# balloon-v02-matt.net
KiCad netlist of a schematic drawn in EAGLE
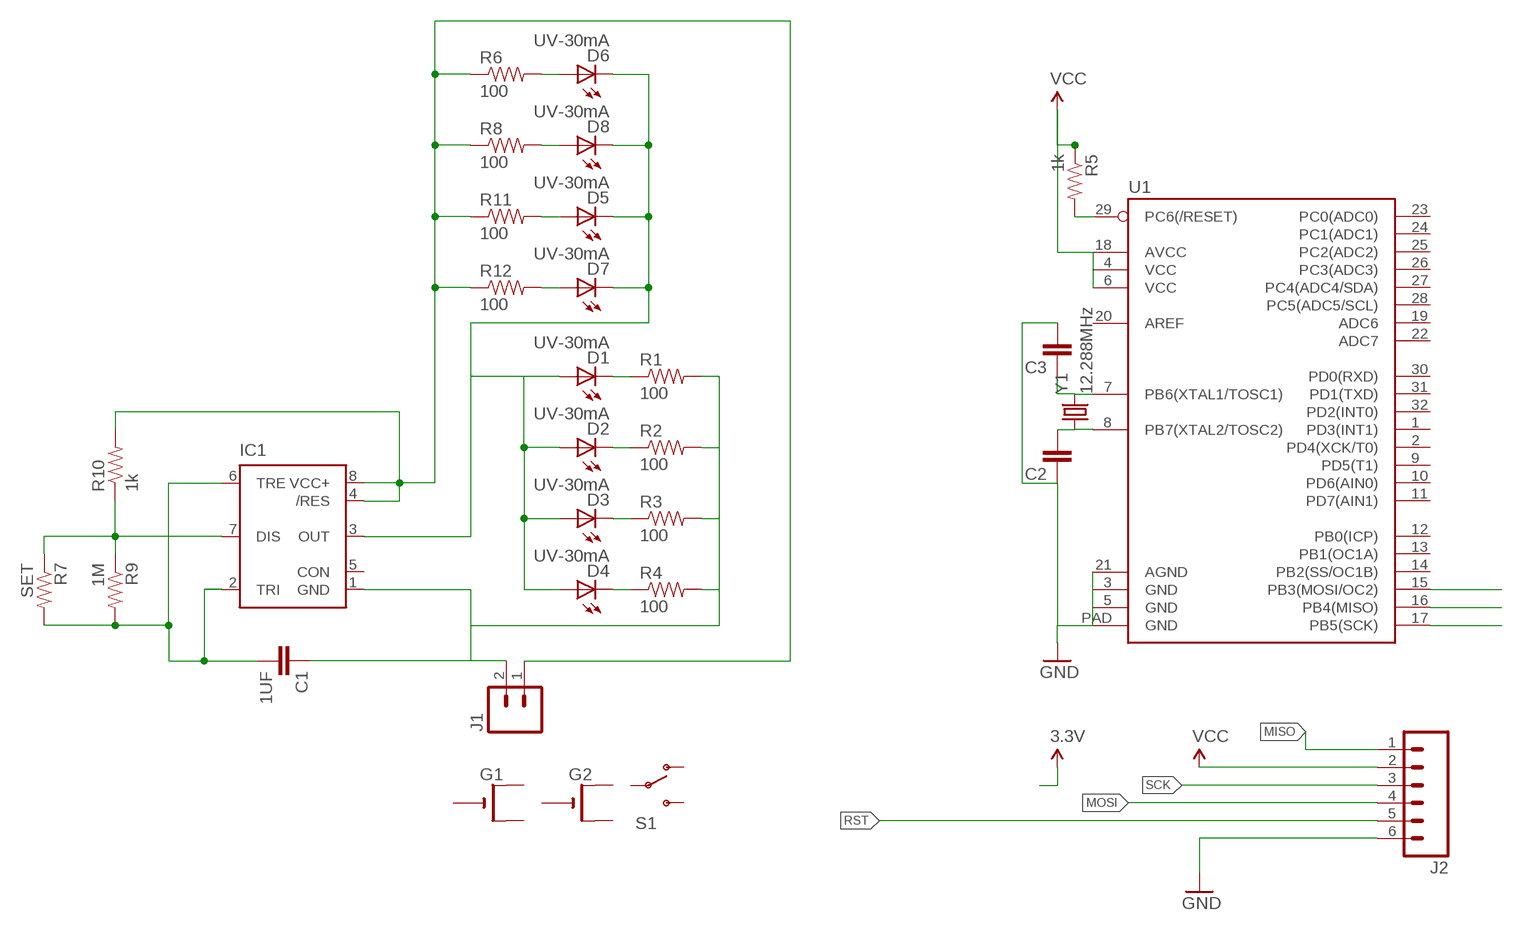
[diagram p0: schematic, sheet 1]

(export (version "E")
  (design (tool "Eeschema 10.0.6"))
  (components
    (comp (ref "C1")
      (value "1UF")
      (footprint "eagle-import:0603-CAP")
      (libsource (lib "eagle-import") (part "CAP0603-CAP"))
    )
    (comp (ref "C2")
      (value "CAP0603-CAP")
      (footprint "eagle-import:0603-CAP")
      (libsource (lib "eagle-import") (part "SparkFun-Passives_CAP0603-CAP"))
    )
    (comp (ref "C3")
      (value "CAP0603-CAP")
      (footprint "eagle-import:0603-CAP")
      (libsource (lib "eagle-import") (part "SparkFun-Passives_CAP0603-CAP"))
    )
    (comp (ref "D1")
      (value "UV-30mA")
      (footprint "eagle-import:CHIPLED_0603")
      (libsource (lib "eagle-import") (part "LEDCHIPLED_0603"))
    )
    (comp (ref "D2")
      (value "UV-30mA")
      (footprint "eagle-import:CHIPLED_0603")
      (libsource (lib "eagle-import") (part "LEDCHIPLED_0603"))
    )
    (comp (ref "D3")
      (value "UV-30mA")
      (footprint "eagle-import:CHIPLED_0603")
      (libsource (lib "eagle-import") (part "LEDCHIPLED_0603"))
    )
    (comp (ref "D4")
      (value "UV-30mA")
      (footprint "eagle-import:CHIPLED_0603")
      (libsource (lib "eagle-import") (part "LEDCHIPLED_0603"))
    )
    (comp (ref "D5")
      (value "UV-30mA")
      (footprint "eagle-import:CHIPLED_0603")
      (libsource (lib "eagle-import") (part "LEDCHIPLED_0603"))
    )
    (comp (ref "D6")
      (value "UV-30mA")
      (footprint "eagle-import:CHIPLED_0603")
      (libsource (lib "eagle-import") (part "LEDCHIPLED_0603"))
    )
    (comp (ref "D7")
      (value "UV-30mA")
      (footprint "eagle-import:CHIPLED_0603")
      (libsource (lib "eagle-import") (part "LEDCHIPLED_0603"))
    )
    (comp (ref "D8")
      (value "UV-30mA")
      (footprint "eagle-import:CHIPLED_0603")
      (libsource (lib "eagle-import") (part "LEDCHIPLED_0603"))
    )
    (comp (ref "G1")
      (value "CR2032SMT")
      (footprint "eagle-import:CR2032-SMD")
      (libsource (lib "eagle-import") (part "CR2032SMT"))
    )
    (comp (ref "G2")
      (value "CR2032SMT")
      (footprint "eagle-import:CR2032-SMD")
      (libsource (lib "eagle-import") (part "CR2032SMT"))
    )
    (comp (ref "IC1")
      (value "NE555D")
      (footprint "eagle-import:SO08")
      (libsource (lib "eagle-import") (part "NE555D"))
    )
    (comp (ref "J1")
      (value "M02PTH3")
      (footprint "eagle-import:1X02_LONGPADS")
      (libsource (lib "eagle-import") (part "M02PTH3"))
    )
    (comp (ref "J2")
      (value "M06SIP_LOCK")
      (footprint "eagle-import:1X06-SIP_LOCK")
      (libsource (lib "eagle-import") (part "M06SIP_LOCK"))
    )
    (comp (ref "R1")
      (value "100")
      (footprint "eagle-import:0603-RES")
      (libsource (lib "eagle-import") (part "RESISTOR0603-RES"))
    )
    (comp (ref "R2")
      (value "100")
      (footprint "eagle-import:0603-RES")
      (libsource (lib "eagle-import") (part "RESISTOR0603-RES"))
    )
    (comp (ref "R3")
      (value "100")
      (footprint "eagle-import:0603-RES")
      (libsource (lib "eagle-import") (part "RESISTOR0603-RES"))
    )
    (comp (ref "R4")
      (value "100")
      (footprint "eagle-import:0603-RES")
      (libsource (lib "eagle-import") (part "RESISTOR0603-RES"))
    )
    (comp (ref "R5")
      (value "1k")
      (footprint "eagle-import:0603-RES")
      (libsource (lib "eagle-import") (part "RESISTOR0603-RES"))
    )
    (comp (ref "R6")
      (value "100")
      (footprint "eagle-import:0603-RES")
      (libsource (lib "eagle-import") (part "RESISTOR0603-RES"))
    )
    (comp (ref "R7")
      (value "SET")
      (footprint "eagle-import:AXIAL-0.3-KIT")
      (libsource (lib "eagle-import") (part "RESISTORKIT"))
    )
    (comp (ref "R8")
      (value "100")
      (footprint "eagle-import:0603-RES")
      (libsource (lib "eagle-import") (part "RESISTOR0603-RES"))
    )
    (comp (ref "R9")
      (value "1M")
      (footprint "eagle-import:0603-RES")
      (libsource (lib "eagle-import") (part "RESISTOR0603-RES"))
    )
    (comp (ref "R10")
      (value "1k")
      (footprint "eagle-import:0603-RES")
      (libsource (lib "eagle-import") (part "RESISTOR0603-RES"))
    )
    (comp (ref "R11")
      (value "100")
      (footprint "eagle-import:0603-RES")
      (libsource (lib "eagle-import") (part "RESISTOR0603-RES"))
    )
    (comp (ref "R12")
      (value "100")
      (footprint "eagle-import:0603-RES")
      (libsource (lib "eagle-import") (part "RESISTOR0603-RES"))
    )
    (comp (ref "S1")
      (value "SWITCH-SPDT-SMD-A")
      (footprint "eagle-import:SWITCH-SPST-SMD-A")
      (libsource (lib "eagle-import") (part "SWITCH-SPDT-SMD-A"))
    )
    (comp (ref "U1")
      (value "ATMEGA328P_MLFMLF32")
      (footprint "eagle-import:MLF32-PAD")
      (libsource (lib "eagle-import") (part "ATMEGA328P_MLFMLF32"))
    )
    (comp (ref "Y1")
      (value "12.288MHz")
      (footprint "eagle-import:CRYSTAL-SMD-5X3")
      (libsource (lib "eagle-import") (part "CRYSTALCRYSTAL-SMD-5X3-12.288MHZ"))
    )
  )
  (nets
    (net (code "2") (name "GND") (class "Default")
      (node (ref "C1") (pin "1") (pinfunction "1_1") (pintype "passive"))
      (node (ref "C2") (pin "1") (pinfunction "1_1") (pintype "passive"))
      (node (ref "C3") (pin "2") (pinfunction "2_2") (pintype "passive"))
      (node (ref "IC1") (pin "1") (pinfunction "GND_1") (pintype "power_in"))
      (node (ref "J1") (pin "2") (pinfunction "2_2") (pintype "passive"))
      (node (ref "J2") (pin "6") (pinfunction "6_6") (pintype "passive"))
      (node (ref "R1") (pin "2") (pinfunction "2_2") (pintype "passive"))
      (node (ref "R2") (pin "2") (pinfunction "2_2") (pintype "passive"))
      (node (ref "R3") (pin "2") (pinfunction "2_2") (pintype "passive"))
      (node (ref "R4") (pin "2") (pinfunction "2_2") (pintype "passive"))
      (node (ref "U1") (pin "21") (pinfunction "AGND_21") (pintype "bidirectional"))
      (node (ref "U1") (pin "3") (pinfunction "GND_3") (pintype "bidirectional"))
      (node (ref "U1") (pin "5") (pinfunction "GND_5") (pintype "bidirectional"))
      (node (ref "U1") (pin "PAD") (pinfunction "GND_PAD") (pintype "bidirectional"))
    )
    (net (code "3") (name "MISO") (class "Default")
      (node (ref "J2") (pin "1") (pinfunction "1_1") (pintype "passive"))
      (node (ref "U1") (pin "16") (pinfunction "PB4(MISO)_16") (pintype "bidirectional"))
    )
    (net (code "4") (name "MOSI") (class "Default")
      (node (ref "J2") (pin "4") (pinfunction "4_4") (pintype "passive"))
      (node (ref "U1") (pin "15") (pinfunction "PB3(MOSI/OC2)_15") (pintype "bidirectional"))
    )
    (net (code "5") (name "Net-(D1-PadC)") (class "Default")
      (node (ref "D1") (pin "C") (pinfunction "C_C") (pintype "passive"))
      (node (ref "R1") (pin "1") (pinfunction "1_1") (pintype "passive"))
    )
    (net (code "6") (name "Net-(D2-PadC)") (class "Default")
      (node (ref "D2") (pin "C") (pinfunction "C_C") (pintype "passive"))
      (node (ref "R2") (pin "1") (pinfunction "1_1") (pintype "passive"))
    )
    (net (code "7") (name "Net-(D3-PadC)") (class "Default")
      (node (ref "D3") (pin "C") (pinfunction "C_C") (pintype "passive"))
      (node (ref "R3") (pin "1") (pinfunction "1_1") (pintype "passive"))
    )
    (net (code "8") (name "Net-(D4-PadC)") (class "Default")
      (node (ref "D4") (pin "C") (pinfunction "C_C") (pintype "passive"))
      (node (ref "R4") (pin "1") (pinfunction "1_1") (pintype "passive"))
    )
    (net (code "9") (name "Net-(D5-PadA)") (class "Default")
      (node (ref "D5") (pin "A") (pinfunction "A_A") (pintype "passive"))
      (node (ref "R11") (pin "2") (pinfunction "2_2") (pintype "passive"))
    )
    (net (code "10") (name "Net-(D6-PadA)") (class "Default")
      (node (ref "D6") (pin "A") (pinfunction "A_A") (pintype "passive"))
      (node (ref "R6") (pin "2") (pinfunction "2_2") (pintype "passive"))
    )
    (net (code "11") (name "Net-(D7-PadA)") (class "Default")
      (node (ref "D7") (pin "A") (pinfunction "A_A") (pintype "passive"))
      (node (ref "R12") (pin "2") (pinfunction "2_2") (pintype "passive"))
    )
    (net (code "12") (name "Net-(D8-PadA)") (class "Default")
      (node (ref "D8") (pin "A") (pinfunction "A_A") (pintype "passive"))
      (node (ref "R8") (pin "2") (pinfunction "2_2") (pintype "passive"))
    )
    (net (code "13") (name "Net-(IC1-DIS)") (class "Default")
      (node (ref "IC1") (pin "7") (pinfunction "DIS_7") (pintype "input"))
      (node (ref "R10") (pin "1") (pinfunction "1_1") (pintype "passive"))
      (node (ref "R7") (pin "P$1") (pinfunction "1_P$1") (pintype "passive"))
      (node (ref "R9") (pin "1") (pinfunction "1_1") (pintype "passive"))
    )
    (net (code "14") (name "Net-(IC1-OUT)") (class "Default")
      (node (ref "D1") (pin "A") (pinfunction "A_A") (pintype "passive"))
      (node (ref "D2") (pin "A") (pinfunction "A_A") (pintype "passive"))
      (node (ref "D3") (pin "A") (pinfunction "A_A") (pintype "passive"))
      (node (ref "D4") (pin "A") (pinfunction "A_A") (pintype "passive"))
      (node (ref "D5") (pin "C") (pinfunction "C_C") (pintype "passive"))
      (node (ref "D6") (pin "C") (pinfunction "C_C") (pintype "passive"))
      (node (ref "D7") (pin "C") (pinfunction "C_C") (pintype "passive"))
      (node (ref "D8") (pin "C") (pinfunction "C_C") (pintype "passive"))
      (node (ref "IC1") (pin "3") (pinfunction "OUT_3") (pintype "output"))
    )
    (net (code "15") (name "Net-(IC1-TRE)") (class "Default")
      (node (ref "C1") (pin "2") (pinfunction "2_2") (pintype "passive"))
      (node (ref "IC1") (pin "2") (pinfunction "TRI_2") (pintype "input"))
      (node (ref "IC1") (pin "6") (pinfunction "TRE_6") (pintype "input"))
      (node (ref "R7") (pin "P$2") (pinfunction "2_P$2") (pintype "passive"))
      (node (ref "R9") (pin "2") (pinfunction "2_2") (pintype "passive"))
    )
    (net (code "16") (name "Net-(U1-PB6(XTAL1{slash}TOSC1))") (class "Default")
      (node (ref "C3") (pin "1") (pinfunction "1_1") (pintype "passive"))
      (node (ref "U1") (pin "7") (pinfunction "PB6(XTAL1/TOSC1)_7") (pintype "bidirectional"))
      (node (ref "Y1") (pin "3") (pinfunction "2_3") (pintype "passive"))
    )
    (net (code "17") (name "Net-(U1-PB7(XTAL2{slash}TOSC2))") (class "Default")
      (node (ref "C2") (pin "2") (pinfunction "2_2") (pintype "passive"))
      (node (ref "U1") (pin "8") (pinfunction "PB7(XTAL2/TOSC2)_8") (pintype "bidirectional"))
      (node (ref "Y1") (pin "1") (pinfunction "1_1") (pintype "passive"))
    )
    (net (code "18") (name "RST") (class "Default")
      (node (ref "J2") (pin "5") (pinfunction "5_5") (pintype "passive"))
      (node (ref "R5") (pin "2") (pinfunction "2_2") (pintype "passive"))
      (node (ref "U1") (pin "29") (pinfunction "PC6(/RESET)_29") (pintype "bidirectional"))
    )
    (net (code "19") (name "SCK") (class "Default")
      (node (ref "J2") (pin "3") (pinfunction "3_3") (pintype "passive"))
      (node (ref "U1") (pin "17") (pinfunction "PB5(SCK)_17") (pintype "bidirectional"))
    )
    (net (code "20") (name "VCC") (class "Default")
      (node (ref "IC1") (pin "4") (pinfunction "/RES_4") (pintype "input"))
      (node (ref "IC1") (pin "8") (pinfunction "VCC+_8") (pintype "power_in"))
      (node (ref "J1") (pin "1") (pinfunction "1_1") (pintype "passive"))
      (node (ref "J2") (pin "2") (pinfunction "2_2") (pintype "passive"))
      (node (ref "R10") (pin "2") (pinfunction "2_2") (pintype "passive"))
      (node (ref "R11") (pin "1") (pinfunction "1_1") (pintype "passive"))
      (node (ref "R12") (pin "1") (pinfunction "1_1") (pintype "passive"))
      (node (ref "R5") (pin "1") (pinfunction "1_1") (pintype "passive"))
      (node (ref "R6") (pin "1") (pinfunction "1_1") (pintype "passive"))
      (node (ref "R8") (pin "1") (pinfunction "1_1") (pintype "passive"))
      (node (ref "U1") (pin "18") (pinfunction "AVCC_18") (pintype "bidirectional"))
      (node (ref "U1") (pin "4") (pinfunction "VCC_4") (pintype "bidirectional"))
      (node (ref "U1") (pin "6") (pinfunction "VCC_6") (pintype "bidirectional"))
    )
    (net (code "21") (name "unconnected-(G1-+-Pad+$1)") (class "Default")
      (node (ref "G1") (pin "+$1") (pinfunction "+_+$1") (pintype "passive"))
    )
    (net (code "22") (name "unconnected-(G1-+1-Pad+$2)") (class "Default")
      (node (ref "G1") (pin "+$2") (pinfunction "+1_+$2") (pintype "passive"))
    )
    (net (code "23") (name "unconnected-(G1-Pad-)") (class "Default")
      (node (ref "G1") (pin "-") (pinfunction "-_-") (pintype "passive"))
    )
    (net (code "24") (name "unconnected-(G2-+-Pad+$1)") (class "Default")
      (node (ref "G2") (pin "+$1") (pinfunction "+_+$1") (pintype "passive"))
    )
    (net (code "25") (name "unconnected-(G2-+1-Pad+$2)") (class "Default")
      (node (ref "G2") (pin "+$2") (pinfunction "+1_+$2") (pintype "passive"))
    )
    (net (code "26") (name "unconnected-(G2-Pad-)") (class "Default")
      (node (ref "G2") (pin "-") (pinfunction "-_-") (pintype "passive"))
    )
    (net (code "27") (name "unconnected-(IC1-CON-Pad5)") (class "Default")
      (node (ref "IC1") (pin "5") (pinfunction "CON_5") (pintype "input"))
    )
    (net (code "28") (name "unconnected-(S1-O-Pad1)") (class "Default")
      (node (ref "S1") (pin "1") (pinfunction "O_1") (pintype "passive"))
    )
    (net (code "29") (name "unconnected-(S1-P-Pad2)") (class "Default")
      (node (ref "S1") (pin "2") (pinfunction "P_2") (pintype "passive"))
    )
    (net (code "30") (name "unconnected-(S1-S-Pad3)") (class "Default")
      (node (ref "S1") (pin "3") (pinfunction "S_3") (pintype "passive"))
    )
    (net (code "31") (name "unconnected-(U1-ADC6-Pad19)") (class "Default")
      (node (ref "U1") (pin "19") (pinfunction "ADC6_19") (pintype "bidirectional"))
    )
    (net (code "32") (name "unconnected-(U1-ADC7-Pad22)") (class "Default")
      (node (ref "U1") (pin "22") (pinfunction "ADC7_22") (pintype "bidirectional"))
    )
    (net (code "33") (name "unconnected-(U1-AREF-Pad20)") (class "Default")
      (node (ref "U1") (pin "20") (pinfunction "AREF_20") (pintype "bidirectional"))
    )
    (net (code "34") (name "unconnected-(U1-PB0(ICP)-Pad12)") (class "Default")
      (node (ref "U1") (pin "12") (pinfunction "PB0(ICP)_12") (pintype "bidirectional"))
    )
    (net (code "35") (name "unconnected-(U1-PB1(OC1A)-Pad13)") (class "Default")
      (node (ref "U1") (pin "13") (pinfunction "PB1(OC1A)_13") (pintype "bidirectional"))
    )
    (net (code "36") (name "unconnected-(U1-PB2(SS{slash}OC1B)-Pad14)") (class "Default")
      (node (ref "U1") (pin "14") (pinfunction "PB2(SS/OC1B)_14") (pintype "bidirectional"))
    )
    (net (code "37") (name "unconnected-(U1-PC0(ADC0)-Pad23)") (class "Default")
      (node (ref "U1") (pin "23") (pinfunction "PC0(ADC0)_23") (pintype "bidirectional"))
    )
    (net (code "38") (name "unconnected-(U1-PC1(ADC1)-Pad24)") (class "Default")
      (node (ref "U1") (pin "24") (pinfunction "PC1(ADC1)_24") (pintype "bidirectional"))
    )
    (net (code "39") (name "unconnected-(U1-PC2(ADC2)-Pad25)") (class "Default")
      (node (ref "U1") (pin "25") (pinfunction "PC2(ADC2)_25") (pintype "bidirectional"))
    )
    (net (code "40") (name "unconnected-(U1-PC3(ADC3)-Pad26)") (class "Default")
      (node (ref "U1") (pin "26") (pinfunction "PC3(ADC3)_26") (pintype "bidirectional"))
    )
    (net (code "41") (name "unconnected-(U1-PC4(ADC4{slash}SDA)-Pad27)") (class "Default")
      (node (ref "U1") (pin "27") (pinfunction "PC4(ADC4/SDA)_27") (pintype "bidirectional"))
    )
    (net (code "42") (name "unconnected-(U1-PC5(ADC5{slash}SCL)-Pad28)") (class "Default")
      (node (ref "U1") (pin "28") (pinfunction "PC5(ADC5/SCL)_28") (pintype "bidirectional"))
    )
    (net (code "43") (name "unconnected-(U1-PD0(RXD)-Pad30)") (class "Default")
      (node (ref "U1") (pin "30") (pinfunction "PD0(RXD)_30") (pintype "bidirectional"))
    )
    (net (code "44") (name "unconnected-(U1-PD1(TXD)-Pad31)") (class "Default")
      (node (ref "U1") (pin "31") (pinfunction "PD1(TXD)_31") (pintype "bidirectional"))
    )
    (net (code "45") (name "unconnected-(U1-PD2(INT0)-Pad32)") (class "Default")
      (node (ref "U1") (pin "32") (pinfunction "PD2(INT0)_32") (pintype "bidirectional"))
    )
    (net (code "46") (name "unconnected-(U1-PD3(INT1)-Pad1)") (class "Default")
      (node (ref "U1") (pin "1") (pinfunction "PD3(INT1)_1") (pintype "bidirectional"))
    )
    (net (code "47") (name "unconnected-(U1-PD4(XCK{slash}T0)-Pad2)") (class "Default")
      (node (ref "U1") (pin "2") (pinfunction "PD4(XCK/T0)_2") (pintype "bidirectional"))
    )
    (net (code "48") (name "unconnected-(U1-PD5(T1)-Pad9)") (class "Default")
      (node (ref "U1") (pin "9") (pinfunction "PD5(T1)_9") (pintype "bidirectional"))
    )
    (net (code "49") (name "unconnected-(U1-PD6(AIN0)-Pad10)") (class "Default")
      (node (ref "U1") (pin "10") (pinfunction "PD6(AIN0)_10") (pintype "bidirectional"))
    )
    (net (code "50") (name "unconnected-(U1-PD7(AIN1)-Pad11)") (class "Default")
      (node (ref "U1") (pin "11") (pinfunction "PD7(AIN1)_11") (pintype "bidirectional"))
    )
  )
)
